# G503.net
KiCad netlist of a schematic drawn in EAGLE
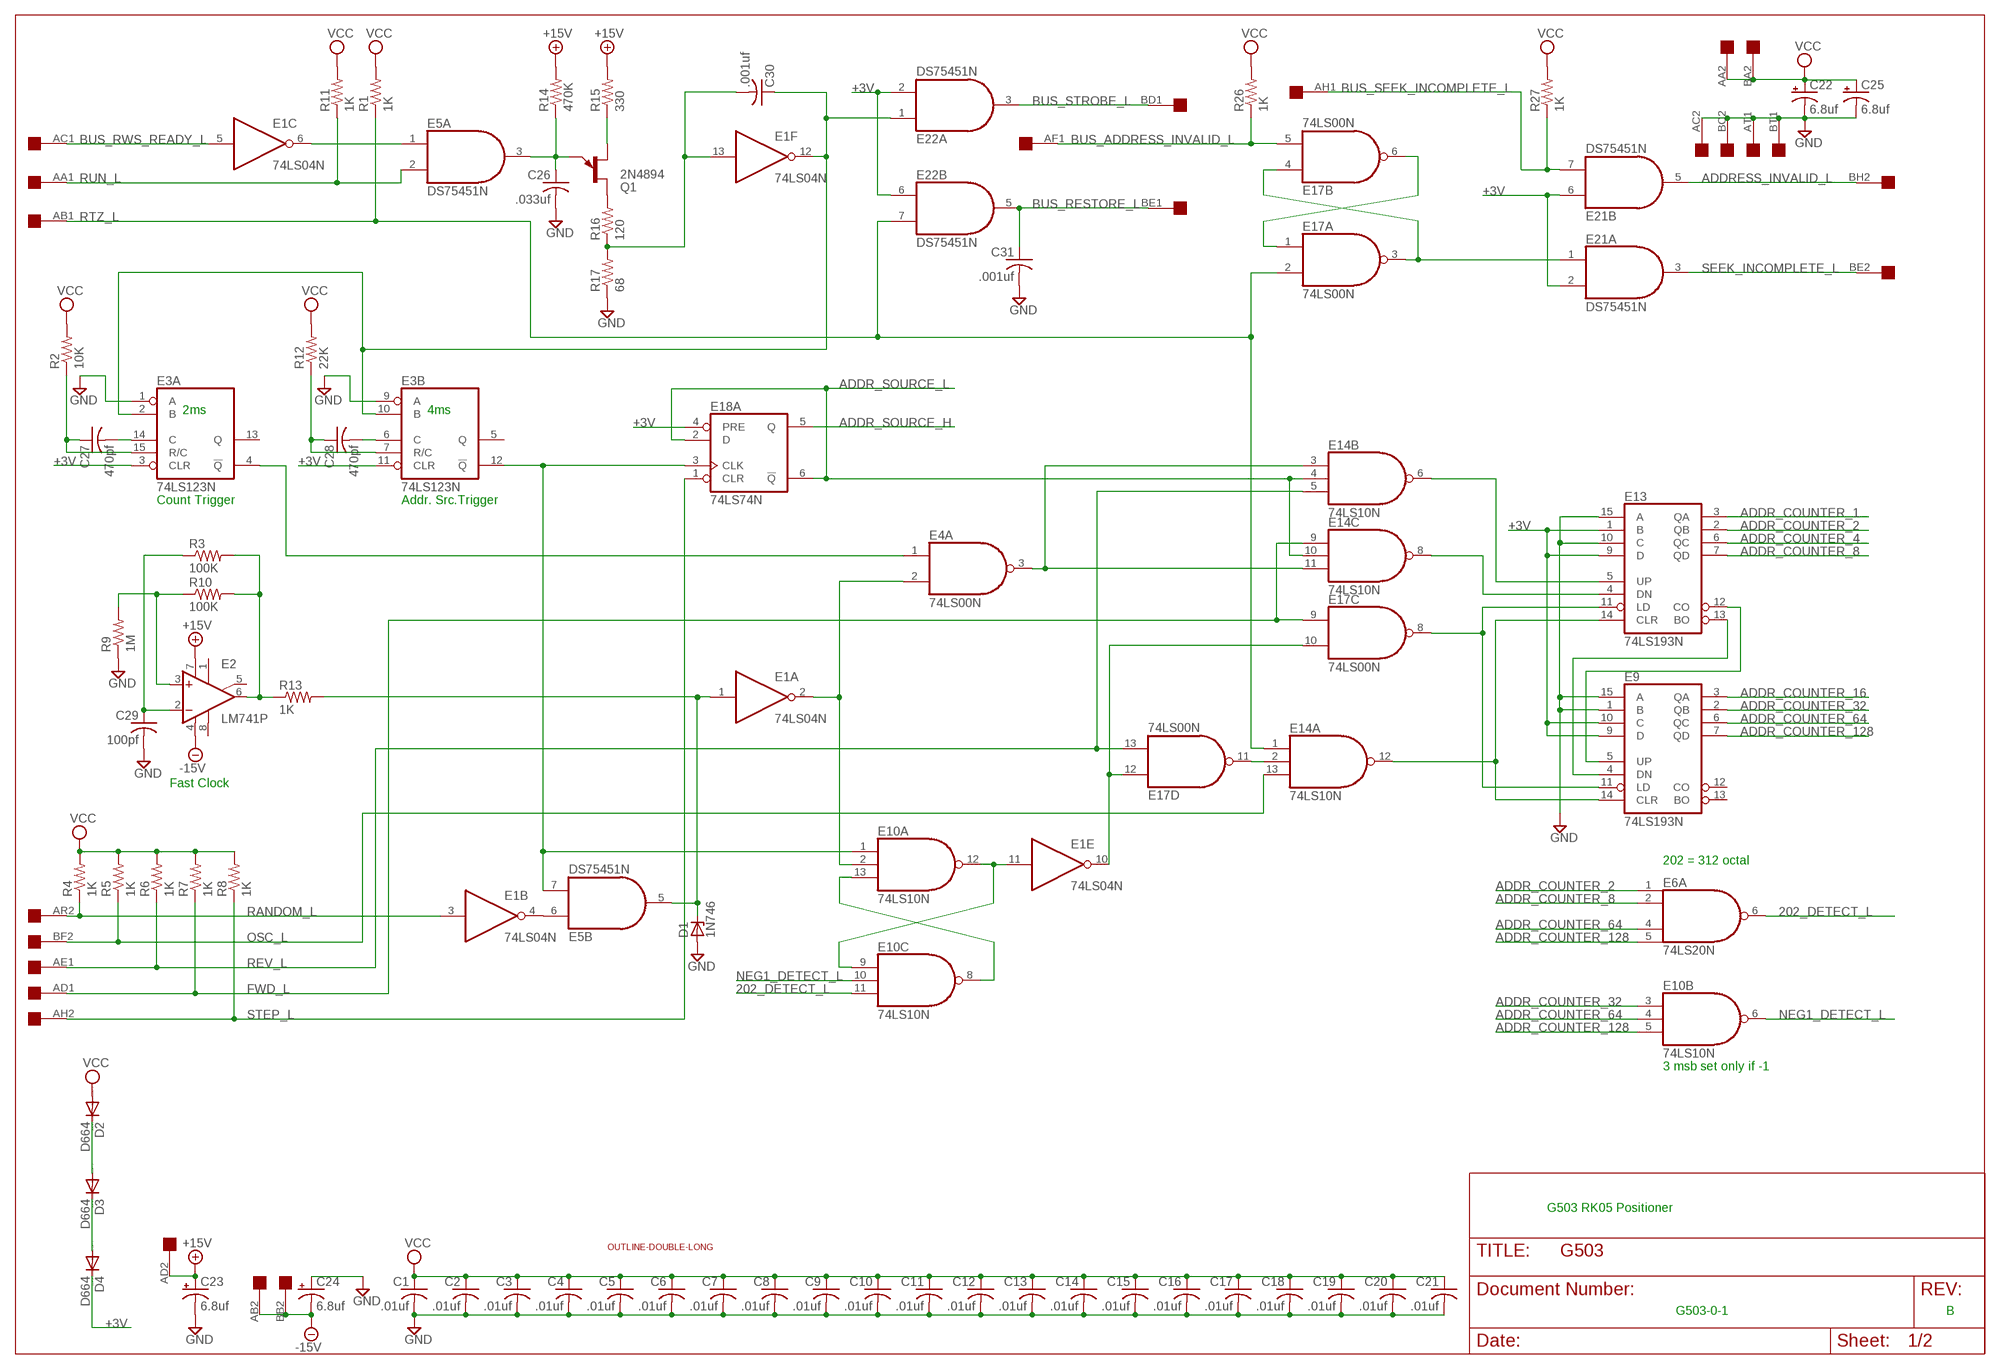
[diagram p0: schematic, sheet 1]
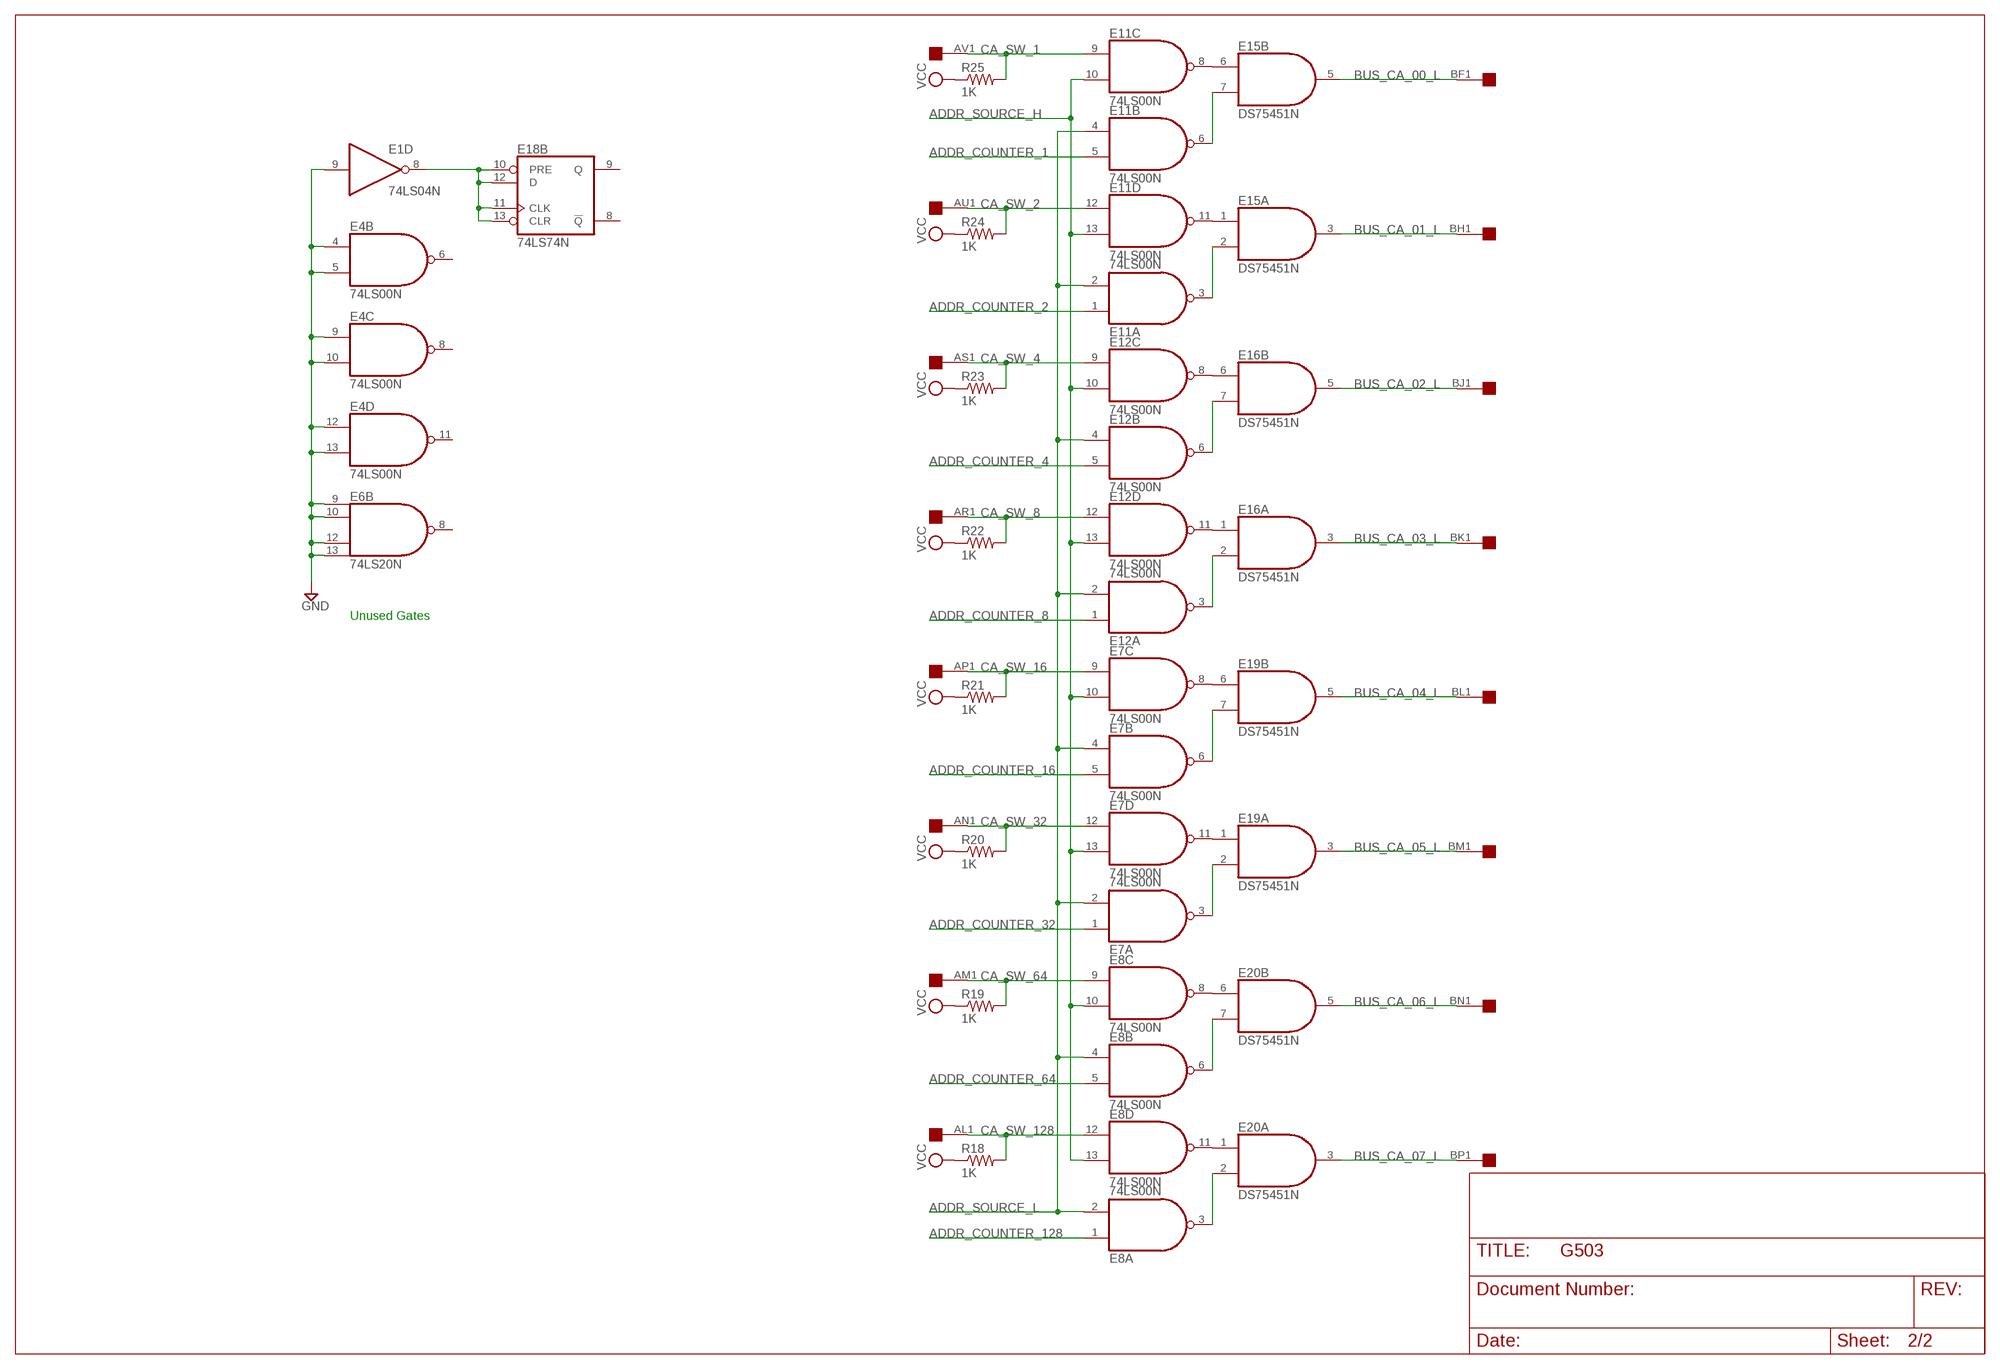
[diagram p1: schematic, sheet 2]

(export (version "E")
  (design (tool "Eeschema 10.0.6"))
  (components
    (comp (ref "AB03")
      (value "DOUBLE")
      (footprint "eagle-import:EDGE-CON4")
      (libsource (lib "eagle-import") (part "DOUBLE"))
    )
    (comp (ref "C1")
      (value ".01uf")
      (footprint "eagle-import:C075-032X103")
      (libsource (lib "eagle-import") (part "C-US075-032X103"))
    )
    (comp (ref "C2")
      (value ".01uf")
      (footprint "eagle-import:C075-032X103")
      (libsource (lib "eagle-import") (part "C-US075-032X103"))
    )
    (comp (ref "C3")
      (value ".01uf")
      (footprint "eagle-import:C075-032X103")
      (libsource (lib "eagle-import") (part "C-US075-032X103"))
    )
    (comp (ref "C4")
      (value ".01uf")
      (footprint "eagle-import:C075-032X103")
      (libsource (lib "eagle-import") (part "C-US075-032X103"))
    )
    (comp (ref "C5")
      (value ".01uf")
      (footprint "eagle-import:C075-032X103")
      (libsource (lib "eagle-import") (part "C-US075-032X103"))
    )
    (comp (ref "C6")
      (value ".01uf")
      (footprint "eagle-import:C075-032X103")
      (libsource (lib "eagle-import") (part "C-US075-032X103"))
    )
    (comp (ref "C7")
      (value ".01uf")
      (footprint "eagle-import:C075-032X103")
      (libsource (lib "eagle-import") (part "C-US075-032X103"))
    )
    (comp (ref "C8")
      (value ".01uf")
      (footprint "eagle-import:C075-032X103")
      (libsource (lib "eagle-import") (part "C-US075-032X103"))
    )
    (comp (ref "C9")
      (value ".01uf")
      (footprint "eagle-import:C075-032X103")
      (libsource (lib "eagle-import") (part "C-US075-032X103"))
    )
    (comp (ref "C10")
      (value ".01uf")
      (footprint "eagle-import:C075-032X103")
      (libsource (lib "eagle-import") (part "C-US075-032X103"))
    )
    (comp (ref "C11")
      (value ".01uf")
      (footprint "eagle-import:C075-032X103")
      (libsource (lib "eagle-import") (part "C-US075-032X103"))
    )
    (comp (ref "C12")
      (value ".01uf")
      (footprint "eagle-import:C075-032X103")
      (libsource (lib "eagle-import") (part "C-US075-032X103"))
    )
    (comp (ref "C13")
      (value ".01uf")
      (footprint "eagle-import:C075-032X103")
      (libsource (lib "eagle-import") (part "C-US075-032X103"))
    )
    (comp (ref "C14")
      (value ".01uf")
      (footprint "eagle-import:C075-032X103")
      (libsource (lib "eagle-import") (part "C-US075-032X103"))
    )
    (comp (ref "C15")
      (value ".01uf")
      (footprint "eagle-import:C075-032X103")
      (libsource (lib "eagle-import") (part "C-US075-032X103"))
    )
    (comp (ref "C16")
      (value ".01uf")
      (footprint "eagle-import:C075-032X103")
      (libsource (lib "eagle-import") (part "C-US075-032X103"))
    )
    (comp (ref "C17")
      (value ".01uf")
      (footprint "eagle-import:C075-032X103")
      (libsource (lib "eagle-import") (part "C-US075-032X103"))
    )
    (comp (ref "C18")
      (value ".01uf")
      (footprint "eagle-import:C075-032X103")
      (libsource (lib "eagle-import") (part "C-US075-032X103"))
    )
    (comp (ref "C19")
      (value ".01uf")
      (footprint "eagle-import:C075-032X103")
      (libsource (lib "eagle-import") (part "C-US075-032X103"))
    )
    (comp (ref "C20")
      (value ".01uf")
      (footprint "eagle-import:C075-032X103")
      (libsource (lib "eagle-import") (part "C-US075-032X103"))
    )
    (comp (ref "C21")
      (value ".01uf")
      (footprint "eagle-import:C075-032X103")
      (libsource (lib "eagle-import") (part "C-US075-032X103"))
    )
    (comp (ref "C22")
      (value "6.8uf")
      (footprint "eagle-import:E25-9")
      (libsource (lib "eagle-import") (part "CPOL-USE25-9AXIAL"))
    )
    (comp (ref "C23")
      (value "6.8uf")
      (footprint "eagle-import:E25-9")
      (libsource (lib "eagle-import") (part "CPOL-USE25-9AXIAL"))
    )
    (comp (ref "C24")
      (value "6.8uf")
      (footprint "eagle-import:E25-9")
      (libsource (lib "eagle-import") (part "CPOL-USE25-9AXIAL"))
    )
    (comp (ref "C25")
      (value "6.8uf")
      (footprint "eagle-import:E25-9")
      (libsource (lib "eagle-import") (part "CPOL-USE25-9AXIAL"))
    )
    (comp (ref "C26")
      (value ".033uf")
      (footprint "eagle-import:C075-032X103")
      (libsource (lib "eagle-import") (part "C-US075-032X103"))
    )
    (comp (ref "C27")
      (value "470pf")
      (footprint "eagle-import:C075-032X103")
      (libsource (lib "eagle-import") (part "C-US075-032X103"))
    )
    (comp (ref "C28")
      (value "470pf")
      (footprint "eagle-import:C075-032X103")
      (libsource (lib "eagle-import") (part "C-US075-032X103"))
    )
    (comp (ref "C29")
      (value "100pf")
      (footprint "eagle-import:C075-032X103")
      (libsource (lib "eagle-import") (part "C-US075-032X103"))
    )
    (comp (ref "C30")
      (value ".001uf")
      (footprint "eagle-import:C075-032X103")
      (libsource (lib "eagle-import") (part "C-US075-032X103"))
    )
    (comp (ref "C31")
      (value ".001uf")
      (footprint "eagle-import:C075-032X103")
      (libsource (lib "eagle-import") (part "C-US075-032X103"))
    )
    (comp (ref "D1")
      (value "1N746")
      (footprint "eagle-import:DO35Z10")
      (libsource (lib "eagle-import") (part "ZENER-DIODEDO35Z10"))
    )
    (comp (ref "D2")
      (value "D664")
      (footprint "eagle-import:DO35-10")
      (libsource (lib "eagle-import") (part "1N4148DO35-10"))
    )
    (comp (ref "D3")
      (value "D664")
      (footprint "eagle-import:DO35-10")
      (libsource (lib "eagle-import") (part "1N4148DO35-10"))
    )
    (comp (ref "D4")
      (value "D664")
      (footprint "eagle-import:DO35-10")
      (libsource (lib "eagle-import") (part "1N4148DO35-10"))
    )
    (comp (ref "E1")
      (value "74LS04N")
      (footprint "eagle-import:DIL14")
      (libsource (lib "eagle-import") (part "7404NLS"))
    )
    (comp (ref "E2")
      (value "LM741P")
      (footprint "eagle-import:DIL08")
      (libsource (lib "eagle-import") (part "741PLM"))
    )
    (comp (ref "E3")
      (value "74LS123N")
      (footprint "eagle-import:DIL16")
      (libsource (lib "eagle-import") (part "74123NLS"))
    )
    (comp (ref "E4")
      (value "74LS00N")
      (footprint "eagle-import:DIL14")
      (libsource (lib "eagle-import") (part "7400NLS"))
    )
    (comp (ref "E5")
      (value "DS75451N")
      (footprint "eagle-import:DIL08")
      (libsource (lib "eagle-import") (part "DS75451N"))
    )
    (comp (ref "E6")
      (value "74LS20N")
      (footprint "eagle-import:DIL14")
      (libsource (lib "eagle-import") (part "7420NLS"))
    )
    (comp (ref "E9")
      (value "74LS193N")
      (footprint "eagle-import:DIL16")
      (libsource (lib "eagle-import") (part "74193NLS"))
    )
    (comp (ref "E10")
      (value "74LS10N")
      (footprint "eagle-import:DIL14")
      (libsource (lib "eagle-import") (part "7410NAS"))
    )
    (comp (ref "E13")
      (value "74LS193N")
      (footprint "eagle-import:DIL16")
      (libsource (lib "eagle-import") (part "74193NLS"))
    )
    (comp (ref "E14")
      (value "74LS10N")
      (footprint "eagle-import:DIL14")
      (libsource (lib "eagle-import") (part "7410NAS"))
    )
    (comp (ref "E17")
      (value "74LS00N")
      (footprint "eagle-import:DIL14")
      (libsource (lib "eagle-import") (part "7400NLS"))
    )
    (comp (ref "E18")
      (value "74LS74N")
      (footprint "eagle-import:DIL14")
      (libsource (lib "eagle-import") (part "7474NLS"))
    )
    (comp (ref "E21")
      (value "DS75451N")
      (footprint "eagle-import:DIL08")
      (libsource (lib "eagle-import") (part "DS75451N"))
    )
    (comp (ref "E22")
      (value "DS75451N")
      (footprint "eagle-import:DIL08")
      (libsource (lib "eagle-import") (part "DS75451N"))
    )
    (comp (ref "Q1")
      (value "2N4894")
      (footprint "eagle-import:TO92E")
      (libsource (lib "eagle-import") (part "2N4870"))
    )
    (comp (ref "R1")
      (value "1K")
      (footprint "eagle-import:0207_10")
      (libsource (lib "eagle-import") (part "R-US_0207/10"))
    )
    (comp (ref "R2")
      (value "10K")
      (footprint "eagle-import:0207_10")
      (libsource (lib "eagle-import") (part "R-US_0207/10"))
    )
    (comp (ref "R3")
      (value "100K")
      (footprint "eagle-import:0207_10")
      (libsource (lib "eagle-import") (part "R-US_0207/10"))
    )
    (comp (ref "R4")
      (value "1K")
      (footprint "eagle-import:0207_10")
      (libsource (lib "eagle-import") (part "R-US_0207/10"))
    )
    (comp (ref "R5")
      (value "1K")
      (footprint "eagle-import:0207_10")
      (libsource (lib "eagle-import") (part "R-US_0207/10"))
    )
    (comp (ref "R6")
      (value "1K")
      (footprint "eagle-import:0207_10")
      (libsource (lib "eagle-import") (part "R-US_0207/10"))
    )
    (comp (ref "R7")
      (value "1K")
      (footprint "eagle-import:0207_10")
      (libsource (lib "eagle-import") (part "R-US_0207/10"))
    )
    (comp (ref "R8")
      (value "1K")
      (footprint "eagle-import:0207_10")
      (libsource (lib "eagle-import") (part "R-US_0207/10"))
    )
    (comp (ref "R9")
      (value "1M")
      (footprint "eagle-import:0207_10")
      (libsource (lib "eagle-import") (part "R-US_0207/10"))
    )
    (comp (ref "R10")
      (value "100K")
      (footprint "eagle-import:0207_10")
      (libsource (lib "eagle-import") (part "R-US_0207/10"))
    )
    (comp (ref "R11")
      (value "1K")
      (footprint "eagle-import:0207_10")
      (libsource (lib "eagle-import") (part "R-US_0207/10"))
    )
    (comp (ref "R12")
      (value "22K")
      (footprint "eagle-import:0207_10")
      (libsource (lib "eagle-import") (part "R-US_0207/10"))
    )
    (comp (ref "R13")
      (value "1K")
      (footprint "eagle-import:0207_10")
      (libsource (lib "eagle-import") (part "R-US_0207/10"))
    )
    (comp (ref "R14")
      (value "470K")
      (footprint "eagle-import:0207_10")
      (libsource (lib "eagle-import") (part "R-US_0207/10"))
    )
    (comp (ref "R15")
      (value "330")
      (footprint "eagle-import:0207_10")
      (libsource (lib "eagle-import") (part "R-US_0207/10"))
    )
    (comp (ref "R16")
      (value "120")
      (footprint "eagle-import:0207_10")
      (libsource (lib "eagle-import") (part "R-US_0207/10"))
    )
    (comp (ref "R17")
      (value "68")
      (footprint "eagle-import:0207_10")
      (libsource (lib "eagle-import") (part "R-US_0207/10"))
    )
    (comp (ref "R26")
      (value "1K")
      (footprint "eagle-import:0207_10")
      (libsource (lib "eagle-import") (part "R-US_0207/10"))
    )
    (comp (ref "R27")
      (value "1K")
      (footprint "eagle-import:0207_10")
      (libsource (lib "eagle-import") (part "R-US_0207/10"))
    )
    (comp (ref "U$1")
      (value "OUTLINE-DOUBLE-LONG")
      (footprint "eagle-import:DOUBLE-LONG")
      (libsource (lib "eagle-import") (part "OUTLINE-DOUBLE-LONG"))
    )
    (comp (ref "E7")
      (value "74LS00N")
      (footprint "eagle-import:DIL14")
      (libsource (lib "eagle-import") (part "7400NLS"))
    )
    (comp (ref "E8")
      (value "74LS00N")
      (footprint "eagle-import:DIL14")
      (libsource (lib "eagle-import") (part "7400NLS"))
    )
    (comp (ref "E11")
      (value "74LS00N")
      (footprint "eagle-import:DIL14")
      (libsource (lib "eagle-import") (part "7400NLS"))
    )
    (comp (ref "E12")
      (value "74LS00N")
      (footprint "eagle-import:DIL14")
      (libsource (lib "eagle-import") (part "7400NLS"))
    )
    (comp (ref "E15")
      (value "DS75451N")
      (footprint "eagle-import:DIL08")
      (libsource (lib "eagle-import") (part "DS75451N"))
    )
    (comp (ref "E16")
      (value "DS75451N")
      (footprint "eagle-import:DIL08")
      (libsource (lib "eagle-import") (part "DS75451N"))
    )
    (comp (ref "E19")
      (value "DS75451N")
      (footprint "eagle-import:DIL08")
      (libsource (lib "eagle-import") (part "DS75451N"))
    )
    (comp (ref "E20")
      (value "DS75451N")
      (footprint "eagle-import:DIL08")
      (libsource (lib "eagle-import") (part "DS75451N"))
    )
    (comp (ref "R18")
      (value "1K")
      (footprint "eagle-import:0207_10")
      (libsource (lib "eagle-import") (part "R-US_0207/10"))
    )
    (comp (ref "R19")
      (value "1K")
      (footprint "eagle-import:0207_10")
      (libsource (lib "eagle-import") (part "R-US_0207/10"))
    )
    (comp (ref "R20")
      (value "1K")
      (footprint "eagle-import:0207_10")
      (libsource (lib "eagle-import") (part "R-US_0207/10"))
    )
    (comp (ref "R21")
      (value "1K")
      (footprint "eagle-import:0207_10")
      (libsource (lib "eagle-import") (part "R-US_0207/10"))
    )
    (comp (ref "R22")
      (value "1K")
      (footprint "eagle-import:0207_10")
      (libsource (lib "eagle-import") (part "R-US_0207/10"))
    )
    (comp (ref "R23")
      (value "1K")
      (footprint "eagle-import:0207_10")
      (libsource (lib "eagle-import") (part "R-US_0207/10"))
    )
    (comp (ref "R24")
      (value "1K")
      (footprint "eagle-import:0207_10")
      (libsource (lib "eagle-import") (part "R-US_0207/10"))
    )
    (comp (ref "R25")
      (value "1K")
      (footprint "eagle-import:0207_10")
      (libsource (lib "eagle-import") (part "R-US_0207/10"))
    )
  )
  (nets
    (net (code "1") (name "+3V") (class "Default")
      (node (ref "D4") (pin "C") (pinfunction "C_C") (pintype "passive"))
      (node (ref "E13") (pin "1") (pinfunction "B_1") (pintype "input"))
      (node (ref "E13") (pin "9") (pinfunction "D_9") (pintype "input"))
      (node (ref "E18") (pin "4") (pinfunction "PRE_4") (pintype "input"))
      (node (ref "E21") (pin "2") (pinfunction "I1_2") (pintype "input"))
      (node (ref "E21") (pin "6") (pinfunction "I0_6") (pintype "input"))
      (node (ref "E22") (pin "2") (pinfunction "I1_2") (pintype "input"))
      (node (ref "E22") (pin "6") (pinfunction "I0_6") (pintype "input"))
      (node (ref "E3") (pin "11") (pinfunction "CLR_11") (pintype "input"))
      (node (ref "E3") (pin "3") (pinfunction "CLR_3") (pintype "input"))
      (node (ref "E9") (pin "10") (pinfunction "C_10") (pintype "input"))
      (node (ref "E9") (pin "9") (pinfunction "D_9") (pintype "input"))
    )
    (net (code "2") (name "+15V") (class "Default")
      (node (ref "AB03") (pin "AD2") (pinfunction "1_AD2") (pintype "bidirectional"))
      (node (ref "C23") (pin "+") (pinfunction "+_+") (pintype "passive"))
      (node (ref "E2") (pin "7") (pinfunction "V+_7") (pintype "power_in"))
      (node (ref "R14") (pin "2") (pinfunction "2_2") (pintype "passive"))
      (node (ref "R15") (pin "2") (pinfunction "2_2") (pintype "passive"))
    )
    (net (code "3") (name "-15V") (class "Default")
      (node (ref "AB03") (pin "AB2") (pinfunction "1_AB2") (pintype "bidirectional"))
      (node (ref "AB03") (pin "BB2") (pinfunction "1_BB2") (pintype "bidirectional"))
      (node (ref "C24") (pin "-") (pinfunction "-_-") (pintype "passive"))
      (node (ref "E2") (pin "4") (pinfunction "V-_4") (pintype "power_in"))
    )
    (net (code "4") (name "202_DETECT_L") (class "Default")
      (node (ref "E10") (pin "11") (pinfunction "I2_11") (pintype "input"))
      (node (ref "E6") (pin "6") (pinfunction "O_6") (pintype "output"))
    )
    (net (code "5") (name "ADDRESS_INVALID_L") (class "Default")
      (node (ref "AB03") (pin "BH2") (pinfunction "1_BH2") (pintype "bidirectional"))
      (node (ref "E21") (pin "5") (pinfunction "O_5") (pintype "open_collector"))
    )
    (net (code "6") (name "ADDR_COUNTER_1") (class "Default")
      (node (ref "E11") (pin "5") (pinfunction "I1_5") (pintype "input"))
      (node (ref "E13") (pin "3") (pinfunction "QA_3") (pintype "output"))
    )
    (net (code "7") (name "ADDR_COUNTER_2") (class "Default")
      (node (ref "E11") (pin "1") (pinfunction "I0_1") (pintype "input"))
      (node (ref "E13") (pin "2") (pinfunction "QB_2") (pintype "output"))
      (node (ref "E6") (pin "1") (pinfunction "I0_1") (pintype "input"))
    )
    (net (code "8") (name "ADDR_COUNTER_4") (class "Default")
      (node (ref "E12") (pin "5") (pinfunction "I1_5") (pintype "input"))
      (node (ref "E13") (pin "6") (pinfunction "QC_6") (pintype "output"))
    )
    (net (code "9") (name "ADDR_COUNTER_8") (class "Default")
      (node (ref "E12") (pin "1") (pinfunction "I0_1") (pintype "input"))
      (node (ref "E13") (pin "7") (pinfunction "QD_7") (pintype "output"))
      (node (ref "E6") (pin "2") (pinfunction "I1_2") (pintype "input"))
    )
    (net (code "10") (name "ADDR_COUNTER_16") (class "Default")
      (node (ref "E7") (pin "5") (pinfunction "I1_5") (pintype "input"))
      (node (ref "E9") (pin "3") (pinfunction "QA_3") (pintype "output"))
    )
    (net (code "11") (name "ADDR_COUNTER_32") (class "Default")
      (node (ref "E10") (pin "3") (pinfunction "I0_3") (pintype "input"))
      (node (ref "E7") (pin "1") (pinfunction "I0_1") (pintype "input"))
      (node (ref "E9") (pin "2") (pinfunction "QB_2") (pintype "output"))
    )
    (net (code "12") (name "ADDR_COUNTER_64") (class "Default")
      (node (ref "E10") (pin "4") (pinfunction "I1_4") (pintype "input"))
      (node (ref "E6") (pin "4") (pinfunction "I2_4") (pintype "input"))
      (node (ref "E8") (pin "5") (pinfunction "I1_5") (pintype "input"))
      (node (ref "E9") (pin "6") (pinfunction "QC_6") (pintype "output"))
    )
    (net (code "13") (name "ADDR_COUNTER_128") (class "Default")
      (node (ref "E10") (pin "5") (pinfunction "I2_5") (pintype "input"))
      (node (ref "E6") (pin "5") (pinfunction "I3_5") (pintype "input"))
      (node (ref "E8") (pin "1") (pinfunction "I0_1") (pintype "input"))
      (node (ref "E9") (pin "7") (pinfunction "QD_7") (pintype "output"))
    )
    (net (code "14") (name "ADDR_SOURCE_H") (class "Default")
      (node (ref "E11") (pin "10") (pinfunction "I1_10") (pintype "input"))
      (node (ref "E11") (pin "13") (pinfunction "I1_13") (pintype "input"))
      (node (ref "E12") (pin "10") (pinfunction "I1_10") (pintype "input"))
      (node (ref "E12") (pin "13") (pinfunction "I1_13") (pintype "input"))
      (node (ref "E18") (pin "5") (pinfunction "Q_5") (pintype "output"))
      (node (ref "E7") (pin "10") (pinfunction "I1_10") (pintype "input"))
      (node (ref "E7") (pin "13") (pinfunction "I1_13") (pintype "input"))
      (node (ref "E8") (pin "10") (pinfunction "I1_10") (pintype "input"))
      (node (ref "E8") (pin "13") (pinfunction "I1_13") (pintype "input"))
    )
    (net (code "15") (name "ADDR_SOURCE_L") (class "Default")
      (node (ref "E11") (pin "2") (pinfunction "I1_2") (pintype "input"))
      (node (ref "E11") (pin "4") (pinfunction "I0_4") (pintype "input"))
      (node (ref "E12") (pin "2") (pinfunction "I1_2") (pintype "input"))
      (node (ref "E12") (pin "4") (pinfunction "I0_4") (pintype "input"))
      (node (ref "E14") (pin "10") (pinfunction "I1_10") (pintype "input"))
      (node (ref "E14") (pin "4") (pinfunction "I1_4") (pintype "input"))
      (node (ref "E18") (pin "2") (pinfunction "D_2") (pintype "input"))
      (node (ref "E18") (pin "6") (pinfunction "~{Q}_6") (pintype "output"))
      (node (ref "E7") (pin "2") (pinfunction "I1_2") (pintype "input"))
      (node (ref "E7") (pin "4") (pinfunction "I0_4") (pintype "input"))
      (node (ref "E8") (pin "2") (pinfunction "I1_2") (pintype "input"))
      (node (ref "E8") (pin "4") (pinfunction "I0_4") (pintype "input"))
    )
    (net (code "16") (name "BUS_ADDRESS_INVALID_L") (class "Default")
      (node (ref "AB03") (pin "AF1") (pinfunction "1_AF1") (pintype "bidirectional"))
      (node (ref "E17") (pin "5") (pinfunction "I1_5") (pintype "input"))
      (node (ref "R26") (pin "1") (pinfunction "1_1") (pintype "passive"))
    )
    (net (code "17") (name "BUS_CA_00_L") (class "Default")
      (node (ref "AB03") (pin "BF1") (pinfunction "1_BF1") (pintype "bidirectional"))
      (node (ref "E15") (pin "5") (pinfunction "O_5") (pintype "open_collector"))
    )
    (net (code "18") (name "BUS_CA_01_L") (class "Default")
      (node (ref "AB03") (pin "BH1") (pinfunction "1_BH1") (pintype "bidirectional"))
      (node (ref "E15") (pin "3") (pinfunction "O_3") (pintype "open_collector"))
    )
    (net (code "19") (name "BUS_CA_02_L") (class "Default")
      (node (ref "AB03") (pin "BJ1") (pinfunction "1_BJ1") (pintype "bidirectional"))
      (node (ref "E16") (pin "5") (pinfunction "O_5") (pintype "open_collector"))
    )
    (net (code "20") (name "BUS_CA_03_L") (class "Default")
      (node (ref "AB03") (pin "BK1") (pinfunction "1_BK1") (pintype "bidirectional"))
      (node (ref "E16") (pin "3") (pinfunction "O_3") (pintype "open_collector"))
    )
    (net (code "21") (name "BUS_CA_04_L") (class "Default")
      (node (ref "AB03") (pin "BL1") (pinfunction "1_BL1") (pintype "bidirectional"))
      (node (ref "E19") (pin "5") (pinfunction "O_5") (pintype "open_collector"))
    )
    (net (code "22") (name "BUS_CA_05_L") (class "Default")
      (node (ref "AB03") (pin "BM1") (pinfunction "1_BM1") (pintype "bidirectional"))
      (node (ref "E19") (pin "3") (pinfunction "O_3") (pintype "open_collector"))
    )
    (net (code "23") (name "BUS_CA_06_L") (class "Default")
      (node (ref "AB03") (pin "BN1") (pinfunction "1_BN1") (pintype "bidirectional"))
      (node (ref "E20") (pin "5") (pinfunction "O_5") (pintype "open_collector"))
    )
    (net (code "24") (name "BUS_CA_07_L") (class "Default")
      (node (ref "AB03") (pin "BP1") (pinfunction "1_BP1") (pintype "bidirectional"))
      (node (ref "E20") (pin "3") (pinfunction "O_3") (pintype "open_collector"))
    )
    (net (code "25") (name "BUS_RESTORE_L") (class "Default")
      (node (ref "AB03") (pin "BE1") (pinfunction "1_BE1") (pintype "bidirectional"))
      (node (ref "C31") (pin "1") (pinfunction "1_1") (pintype "passive"))
      (node (ref "E22") (pin "5") (pinfunction "O_5") (pintype "open_collector"))
    )
    (net (code "26") (name "BUS_RWS_READY_L") (class "Default")
      (node (ref "AB03") (pin "AC1") (pinfunction "1_AC1") (pintype "bidirectional"))
      (node (ref "E1") (pin "5") (pinfunction "I_5") (pintype "input"))
    )
    (net (code "27") (name "BUS_SEEK_INCOMPLETE_L") (class "Default")
      (node (ref "AB03") (pin "AH1") (pinfunction "1_AH1") (pintype "bidirectional"))
      (node (ref "E21") (pin "7") (pinfunction "I1_7") (pintype "input"))
      (node (ref "R27") (pin "1") (pinfunction "1_1") (pintype "passive"))
    )
    (net (code "28") (name "BUS_STROBE_L") (class "Default")
      (node (ref "AB03") (pin "BD1") (pinfunction "1_BD1") (pintype "bidirectional"))
      (node (ref "E22") (pin "3") (pinfunction "O_3") (pintype "open_collector"))
    )
    (net (code "29") (name "CA_SW_1") (class "Default")
      (node (ref "AB03") (pin "AV1") (pinfunction "1_AV1") (pintype "bidirectional"))
      (node (ref "E11") (pin "9") (pinfunction "I0_9") (pintype "input"))
      (node (ref "R25") (pin "2") (pinfunction "2_2") (pintype "passive"))
    )
    (net (code "30") (name "CA_SW_2") (class "Default")
      (node (ref "AB03") (pin "AU1") (pinfunction "1_AU1") (pintype "bidirectional"))
      (node (ref "E11") (pin "12") (pinfunction "I0_12") (pintype "input"))
      (node (ref "R24") (pin "2") (pinfunction "2_2") (pintype "passive"))
    )
    (net (code "31") (name "CA_SW_4") (class "Default")
      (node (ref "AB03") (pin "AS1") (pinfunction "1_AS1") (pintype "bidirectional"))
      (node (ref "E12") (pin "9") (pinfunction "I0_9") (pintype "input"))
      (node (ref "R23") (pin "2") (pinfunction "2_2") (pintype "passive"))
    )
    (net (code "32") (name "CA_SW_8") (class "Default")
      (node (ref "AB03") (pin "AR1") (pinfunction "1_AR1") (pintype "bidirectional"))
      (node (ref "E12") (pin "12") (pinfunction "I0_12") (pintype "input"))
      (node (ref "R22") (pin "2") (pinfunction "2_2") (pintype "passive"))
    )
    (net (code "33") (name "CA_SW_16") (class "Default")
      (node (ref "AB03") (pin "AP1") (pinfunction "1_AP1") (pintype "bidirectional"))
      (node (ref "E7") (pin "9") (pinfunction "I0_9") (pintype "input"))
      (node (ref "R21") (pin "2") (pinfunction "2_2") (pintype "passive"))
    )
    (net (code "34") (name "CA_SW_32") (class "Default")
      (node (ref "AB03") (pin "AN1") (pinfunction "1_AN1") (pintype "bidirectional"))
      (node (ref "E7") (pin "12") (pinfunction "I0_12") (pintype "input"))
      (node (ref "R20") (pin "2") (pinfunction "2_2") (pintype "passive"))
    )
    (net (code "35") (name "CA_SW_64") (class "Default")
      (node (ref "AB03") (pin "AM1") (pinfunction "1_AM1") (pintype "bidirectional"))
      (node (ref "E8") (pin "9") (pinfunction "I0_9") (pintype "input"))
      (node (ref "R19") (pin "2") (pinfunction "2_2") (pintype "passive"))
    )
    (net (code "36") (name "CA_SW_128") (class "Default")
      (node (ref "AB03") (pin "AL1") (pinfunction "1_AL1") (pintype "bidirectional"))
      (node (ref "E8") (pin "12") (pinfunction "I0_12") (pintype "input"))
      (node (ref "R18") (pin "2") (pinfunction "2_2") (pintype "passive"))
    )
    (net (code "37") (name "FWD_L") (class "Default")
      (node (ref "AB03") (pin "AD1") (pinfunction "1_AD1") (pintype "bidirectional"))
      (node (ref "E14") (pin "9") (pinfunction "I0_9") (pintype "input"))
      (node (ref "E17") (pin "9") (pinfunction "I0_9") (pintype "input"))
      (node (ref "R7") (pin "1") (pinfunction "1_1") (pintype "passive"))
    )
    (net (code "38") (name "GND") (class "Default")
      (node (ref "AB03") (pin "AC2") (pinfunction "1_AC2") (pintype "bidirectional"))
      (node (ref "AB03") (pin "AT1") (pinfunction "1_AT1") (pintype "bidirectional"))
      (node (ref "AB03") (pin "BC2") (pinfunction "1_BC2") (pintype "bidirectional"))
      (node (ref "AB03") (pin "BT1") (pinfunction "1_BT1") (pintype "bidirectional"))
      (node (ref "C1") (pin "2") (pinfunction "2_2") (pintype "passive"))
      (node (ref "C10") (pin "2") (pinfunction "2_2") (pintype "passive"))
      (node (ref "C11") (pin "2") (pinfunction "2_2") (pintype "passive"))
      (node (ref "C12") (pin "2") (pinfunction "2_2") (pintype "passive"))
      (node (ref "C13") (pin "2") (pinfunction "2_2") (pintype "passive"))
      (node (ref "C14") (pin "2") (pinfunction "2_2") (pintype "passive"))
      (node (ref "C15") (pin "2") (pinfunction "2_2") (pintype "passive"))
      (node (ref "C16") (pin "2") (pinfunction "2_2") (pintype "passive"))
      (node (ref "C17") (pin "2") (pinfunction "2_2") (pintype "passive"))
      (node (ref "C18") (pin "2") (pinfunction "2_2") (pintype "passive"))
      (node (ref "C19") (pin "2") (pinfunction "2_2") (pintype "passive"))
      (node (ref "C2") (pin "2") (pinfunction "2_2") (pintype "passive"))
      (node (ref "C20") (pin "2") (pinfunction "2_2") (pintype "passive"))
      (node (ref "C21") (pin "2") (pinfunction "2_2") (pintype "passive"))
      (node (ref "C22") (pin "-") (pinfunction "-_-") (pintype "passive"))
      (node (ref "C23") (pin "-") (pinfunction "-_-") (pintype "passive"))
      (node (ref "C24") (pin "+") (pinfunction "+_+") (pintype "passive"))
      (node (ref "C25") (pin "-") (pinfunction "-_-") (pintype "passive"))
      (node (ref "C26") (pin "2") (pinfunction "2_2") (pintype "passive"))
      (node (ref "C29") (pin "2") (pinfunction "2_2") (pintype "passive"))
      (node (ref "C3") (pin "2") (pinfunction "2_2") (pintype "passive"))
      (node (ref "C31") (pin "2") (pinfunction "2_2") (pintype "passive"))
      (node (ref "C4") (pin "2") (pinfunction "2_2") (pintype "passive"))
      (node (ref "C5") (pin "2") (pinfunction "2_2") (pintype "passive"))
      (node (ref "C6") (pin "2") (pinfunction "2_2") (pintype "passive"))
      (node (ref "C7") (pin "2") (pinfunction "2_2") (pintype "passive"))
      (node (ref "C8") (pin "2") (pinfunction "2_2") (pintype "passive"))
      (node (ref "C9") (pin "2") (pinfunction "2_2") (pintype "passive"))
      (node (ref "D1") (pin "A") (pinfunction "A_A") (pintype "passive"))
      (node (ref "E1") (pin "9") (pinfunction "I_9") (pintype "input"))
      (node (ref "E13") (pin "10") (pinfunction "C_10") (pintype "input"))
      (node (ref "E13") (pin "15") (pinfunction "A_15") (pintype "input"))
      (node (ref "E3") (pin "1") (pinfunction "A_1") (pintype "input"))
      (node (ref "E3") (pin "9") (pinfunction "A_9") (pintype "input"))
      (node (ref "E4") (pin "10") (pinfunction "I1_10") (pintype "input"))
      (node (ref "E4") (pin "12") (pinfunction "I0_12") (pintype "input"))
      (node (ref "E4") (pin "13") (pinfunction "I1_13") (pintype "input"))
      (node (ref "E4") (pin "4") (pinfunction "I0_4") (pintype "input"))
      (node (ref "E4") (pin "5") (pinfunction "I1_5") (pintype "input"))
      (node (ref "E4") (pin "9") (pinfunction "I0_9") (pintype "input"))
      (node (ref "E6") (pin "10") (pinfunction "I1_10") (pintype "input"))
      (node (ref "E6") (pin "12") (pinfunction "I2_12") (pintype "input"))
      (node (ref "E6") (pin "13") (pinfunction "I3_13") (pintype "input"))
      (node (ref "E6") (pin "9") (pinfunction "I0_9") (pintype "input"))
      (node (ref "E9") (pin "1") (pinfunction "B_1") (pintype "input"))
      (node (ref "E9") (pin "15") (pinfunction "A_15") (pintype "input"))
      (node (ref "R17") (pin "1") (pinfunction "1_1") (pintype "passive"))
      (node (ref "R9") (pin "1") (pinfunction "1_1") (pintype "passive"))
    )
    (net (code "39") (name "NEG1_DETECT_L") (class "Default")
      (node (ref "E10") (pin "10") (pinfunction "I1_10") (pintype "input"))
      (node (ref "E10") (pin "6") (pinfunction "O_6") (pintype "output"))
    )
    (net (code "40") (name "Net-(D2-PadC)") (class "Default")
      (node (ref "D2") (pin "C") (pinfunction "C_C") (pintype "passive"))
      (node (ref "D3") (pin "A") (pinfunction "A_A") (pintype "passive"))
    )
    (net (code "41") (name "Net-(D3-PadC)") (class "Default")
      (node (ref "D3") (pin "C") (pinfunction "C_C") (pintype "passive"))
      (node (ref "D4") (pin "A") (pinfunction "A_A") (pintype "passive"))
    )
    (net (code "42") (name "Net-(E1A-I)") (class "Default")
      (node (ref "D1") (pin "C") (pinfunction "C_C") (pintype "passive"))
      (node (ref "E1") (pin "1") (pinfunction "I_1") (pintype "input"))
      (node (ref "E5") (pin "5") (pinfunction "O_5") (pintype "open_collector"))
      (node (ref "R13") (pin "2") (pinfunction "2_2") (pintype "passive"))
    )
    (net (code "43") (name "Net-(E1B-O)") (class "Default")
      (node (ref "E1") (pin "4") (pinfunction "O_4") (pintype "output"))
      (node (ref "E5") (pin "6") (pinfunction "I0_6") (pintype "input"))
    )
    (net (code "44") (name "Net-(E1C-O)") (class "Default")
      (node (ref "E1") (pin "6") (pinfunction "O_6") (pintype "output"))
      (node (ref "E5") (pin "1") (pinfunction "I0_1") (pintype "input"))
    )
    (net (code "45") (name "Net-(E1F-I)") (class "Default")
      (node (ref "C30") (pin "2") (pinfunction "2_2") (pintype "passive"))
      (node (ref "E1") (pin "13") (pinfunction "I_13") (pintype "input"))
      (node (ref "R16") (pin "1") (pinfunction "1_1") (pintype "passive"))
      (node (ref "R17") (pin "2") (pinfunction "2_2") (pintype "passive"))
    )
    (net (code "46") (name "Net-(E1F-O)") (class "Default")
      (node (ref "C30") (pin "1") (pinfunction "1_1") (pintype "passive"))
      (node (ref "E1") (pin "12") (pinfunction "O_12") (pintype "output"))
      (node (ref "E22") (pin "1") (pinfunction "I0_1") (pintype "input"))
      (node (ref "E3") (pin "10") (pinfunction "B_10") (pintype "input"))
      (node (ref "E3") (pin "2") (pinfunction "B_2") (pintype "input"))
    )
    (net (code "47") (name "Net-(E2-+IN)") (class "Default")
      (node (ref "E2") (pin "3") (pinfunction "+IN_3") (pintype "input"))
      (node (ref "R10") (pin "1") (pinfunction "1_1") (pintype "passive"))
      (node (ref "R9") (pin "2") (pinfunction "2_2") (pintype "passive"))
    )
    (net (code "48") (name "Net-(E2--IN)") (class "Default")
      (node (ref "C29") (pin "1") (pinfunction "1_1") (pintype "passive"))
      (node (ref "E2") (pin "2") (pinfunction "-IN_2") (pintype "input"))
      (node (ref "R3") (pin "1") (pinfunction "1_1") (pintype "passive"))
    )
    (net (code "49") (name "Net-(E2-OUT)") (class "Default")
      (node (ref "E2") (pin "6") (pinfunction "OUT_6") (pintype "output"))
      (node (ref "R10") (pin "2") (pinfunction "2_2") (pintype "passive"))
      (node (ref "R13") (pin "1") (pinfunction "1_1") (pintype "passive"))
      (node (ref "R3") (pin "2") (pinfunction "2_2") (pintype "passive"))
    )
    (net (code "50") (name "Net-(E3A-C)") (class "Default")
      (node (ref "C27") (pin "2") (pinfunction "2_2") (pintype "passive"))
      (node (ref "E3") (pin "14") (pinfunction "C_14") (pintype "input"))
    )
    (net (code "51") (name "Net-(E3A-R{slash}C)") (class "Default")
      (node (ref "C27") (pin "1") (pinfunction "1_1") (pintype "passive"))
      (node (ref "E3") (pin "15") (pinfunction "R/C_15") (pintype "input"))
      (node (ref "R2") (pin "1") (pinfunction "1_1") (pintype "passive"))
    )
    (net (code "52") (name "Net-(E3A-~{Q})") (class "Default")
      (node (ref "E3") (pin "4") (pinfunction "~{Q}_4") (pintype "output"))
      (node (ref "E4") (pin "1") (pinfunction "I0_1") (pintype "input"))
    )
    (net (code "53") (name "Net-(E3B-C)") (class "Default")
      (node (ref "C28") (pin "2") (pinfunction "2_2") (pintype "passive"))
      (node (ref "E3") (pin "6") (pinfunction "C_6") (pintype "input"))
    )
    (net (code "54") (name "Net-(E3B-R{slash}C)") (class "Default")
      (node (ref "C28") (pin "1") (pinfunction "1_1") (pintype "passive"))
      (node (ref "E3") (pin "7") (pinfunction "R/C_7") (pintype "input"))
      (node (ref "R12") (pin "1") (pinfunction "1_1") (pintype "passive"))
    )
    (net (code "55") (name "Net-(E5A-O)") (class "Default")
      (node (ref "C26") (pin "1") (pinfunction "1_1") (pintype "passive"))
      (node (ref "E5") (pin "3") (pinfunction "O_3") (pintype "open_collector"))
      (node (ref "Q1") (pin "E") (pinfunction "E_E") (pintype "passive"))
      (node (ref "R14") (pin "1") (pinfunction "1_1") (pintype "passive"))
    )
    (net (code "56") (name "Net-(E10A-I0)") (class "Default")
      (node (ref "E10") (pin "1") (pinfunction "I0_1") (pintype "input"))
      (node (ref "E18") (pin "3") (pinfunction "CLK_3") (pintype "input"))
      (node (ref "E3") (pin "12") (pinfunction "~{Q}_12") (pintype "output"))
      (node (ref "E5") (pin "7") (pinfunction "I1_7") (pintype "input"))
    )
    (net (code "57") (name "Net-(E10A-I1)") (class "Default")
      (node (ref "E1") (pin "2") (pinfunction "O_2") (pintype "output"))
      (node (ref "E10") (pin "2") (pinfunction "I1_2") (pintype "input"))
      (node (ref "E4") (pin "2") (pinfunction "I1_2") (pintype "input"))
    )
    (net (code "58") (name "Net-(E10A-I2)") (class "Default")
      (node (ref "E10") (pin "13") (pinfunction "I2_13") (pintype "input"))
      (node (ref "E10") (pin "8") (pinfunction "O_8") (pintype "output"))
    )
    (net (code "59") (name "Net-(E10A-O)") (class "Default")
      (node (ref "E1") (pin "11") (pinfunction "I_11") (pintype "input"))
      (node (ref "E10") (pin "12") (pinfunction "O_12") (pintype "output"))
      (node (ref "E10") (pin "9") (pinfunction "I0_9") (pintype "input"))
    )
    (net (code "60") (name "Net-(E11A-O)") (class "Default")
      (node (ref "E11") (pin "3") (pinfunction "O_3") (pintype "output"))
      (node (ref "E15") (pin "2") (pinfunction "I1_2") (pintype "input"))
    )
    (net (code "61") (name "Net-(E11B-O)") (class "Default")
      (node (ref "E11") (pin "6") (pinfunction "O_6") (pintype "output"))
      (node (ref "E15") (pin "7") (pinfunction "I1_7") (pintype "input"))
    )
    (net (code "62") (name "Net-(E11C-O)") (class "Default")
      (node (ref "E11") (pin "8") (pinfunction "O_8") (pintype "output"))
      (node (ref "E15") (pin "6") (pinfunction "I0_6") (pintype "input"))
    )
    (net (code "63") (name "Net-(E11D-O)") (class "Default")
      (node (ref "E11") (pin "11") (pinfunction "O_11") (pintype "output"))
      (node (ref "E15") (pin "1") (pinfunction "I0_1") (pintype "input"))
    )
    (net (code "64") (name "Net-(E12A-O)") (class "Default")
      (node (ref "E12") (pin "3") (pinfunction "O_3") (pintype "output"))
      (node (ref "E16") (pin "2") (pinfunction "I1_2") (pintype "input"))
    )
    (net (code "65") (name "Net-(E12B-O)") (class "Default")
      (node (ref "E12") (pin "6") (pinfunction "O_6") (pintype "output"))
      (node (ref "E16") (pin "7") (pinfunction "I1_7") (pintype "input"))
    )
    (net (code "66") (name "Net-(E12C-O)") (class "Default")
      (node (ref "E12") (pin "8") (pinfunction "O_8") (pintype "output"))
      (node (ref "E16") (pin "6") (pinfunction "I0_6") (pintype "input"))
    )
    (net (code "67") (name "Net-(E12D-O)") (class "Default")
      (node (ref "E12") (pin "11") (pinfunction "O_11") (pintype "output"))
      (node (ref "E16") (pin "1") (pinfunction "I0_1") (pintype "input"))
    )
    (net (code "68") (name "Net-(E13A-BO)") (class "Default")
      (node (ref "E13") (pin "13") (pinfunction "BO_13") (pintype "output"))
      (node (ref "E9") (pin "4") (pinfunction "DN_4") (pintype "input"))
    )
    (net (code "69") (name "Net-(E13A-CLR)") (class "Default")
      (node (ref "E13") (pin "14") (pinfunction "CLR_14") (pintype "input"))
      (node (ref "E14") (pin "12") (pinfunction "O_12") (pintype "output"))
      (node (ref "E9") (pin "14") (pinfunction "CLR_14") (pintype "input"))
    )
    (net (code "70") (name "Net-(E13A-CO)") (class "Default")
      (node (ref "E13") (pin "12") (pinfunction "CO_12") (pintype "output"))
      (node (ref "E9") (pin "5") (pinfunction "UP_5") (pintype "input"))
    )
    (net (code "71") (name "Net-(E13A-DN)") (class "Default")
      (node (ref "E13") (pin "4") (pinfunction "DN_4") (pintype "input"))
      (node (ref "E14") (pin "8") (pinfunction "O_8") (pintype "output"))
    )
    (net (code "72") (name "Net-(E13A-LD)") (class "Default")
      (node (ref "E13") (pin "11") (pinfunction "LD_11") (pintype "input"))
      (node (ref "E17") (pin "8") (pinfunction "O_8") (pintype "output"))
      (node (ref "E9") (pin "11") (pinfunction "LD_11") (pintype "input"))
    )
    (net (code "73") (name "Net-(E13A-UP)") (class "Default")
      (node (ref "E13") (pin "5") (pinfunction "UP_5") (pintype "input"))
      (node (ref "E14") (pin "6") (pinfunction "O_6") (pintype "output"))
    )
    (net (code "74") (name "Net-(E14A-I1)") (class "Default")
      (node (ref "E14") (pin "2") (pinfunction "I1_2") (pintype "input"))
      (node (ref "E17") (pin "11") (pinfunction "O_11") (pintype "output"))
    )
    (net (code "75") (name "Net-(E14B-I0)") (class "Default")
      (node (ref "E14") (pin "11") (pinfunction "I2_11") (pintype "input"))
      (node (ref "E14") (pin "3") (pinfunction "I0_3") (pintype "input"))
      (node (ref "E4") (pin "3") (pinfunction "O_3") (pintype "output"))
    )
    (net (code "76") (name "Net-(E17A-I0)") (class "Default")
      (node (ref "E17") (pin "1") (pinfunction "I0_1") (pintype "input"))
      (node (ref "E17") (pin "6") (pinfunction "O_6") (pintype "output"))
    )
    (net (code "77") (name "Net-(E17A-O)") (class "Default")
      (node (ref "E17") (pin "3") (pinfunction "O_3") (pintype "output"))
      (node (ref "E17") (pin "4") (pinfunction "I0_4") (pintype "input"))
      (node (ref "E21") (pin "1") (pinfunction "I0_1") (pintype "input"))
    )
    (net (code "78") (name "Net-(E17C-I1)") (class "Default")
      (node (ref "E1") (pin "10") (pinfunction "O_10") (pintype "output"))
      (node (ref "E17") (pin "10") (pinfunction "I1_10") (pintype "input"))
      (node (ref "E17") (pin "12") (pinfunction "I0_12") (pintype "input"))
    )
    (net (code "79") (name "Net-(E18B-CLK)") (class "Default")
      (node (ref "E1") (pin "8") (pinfunction "O_8") (pintype "output"))
      (node (ref "E18") (pin "10") (pinfunction "PRE_10") (pintype "input"))
      (node (ref "E18") (pin "11") (pinfunction "CLK_11") (pintype "input"))
      (node (ref "E18") (pin "12") (pinfunction "D_12") (pintype "input"))
      (node (ref "E18") (pin "13") (pinfunction "CLR_13") (pintype "input"))
    )
    (net (code "80") (name "Net-(E19A-I0)") (class "Default")
      (node (ref "E19") (pin "1") (pinfunction "I0_1") (pintype "input"))
      (node (ref "E7") (pin "11") (pinfunction "O_11") (pintype "output"))
    )
    (net (code "81") (name "Net-(E19A-I1)") (class "Default")
      (node (ref "E19") (pin "2") (pinfunction "I1_2") (pintype "input"))
      (node (ref "E7") (pin "3") (pinfunction "O_3") (pintype "output"))
    )
    (net (code "82") (name "Net-(E19B-I0)") (class "Default")
      (node (ref "E19") (pin "6") (pinfunction "I0_6") (pintype "input"))
      (node (ref "E7") (pin "8") (pinfunction "O_8") (pintype "output"))
    )
    (net (code "83") (name "Net-(E19B-I1)") (class "Default")
      (node (ref "E19") (pin "7") (pinfunction "I1_7") (pintype "input"))
      (node (ref "E7") (pin "6") (pinfunction "O_6") (pintype "output"))
    )
    (net (code "84") (name "Net-(E20A-I0)") (class "Default")
      (node (ref "E20") (pin "1") (pinfunction "I0_1") (pintype "input"))
      (node (ref "E8") (pin "11") (pinfunction "O_11") (pintype "output"))
    )
    (net (code "85") (name "Net-(E20A-I1)") (class "Default")
      (node (ref "E20") (pin "2") (pinfunction "I1_2") (pintype "input"))
      (node (ref "E8") (pin "3") (pinfunction "O_3") (pintype "output"))
    )
    (net (code "86") (name "Net-(E20B-I0)") (class "Default")
      (node (ref "E20") (pin "6") (pinfunction "I0_6") (pintype "input"))
      (node (ref "E8") (pin "8") (pinfunction "O_8") (pintype "output"))
    )
    (net (code "87") (name "Net-(E20B-I1)") (class "Default")
      (node (ref "E20") (pin "7") (pinfunction "I1_7") (pintype "input"))
      (node (ref "E8") (pin "6") (pinfunction "O_6") (pintype "output"))
    )
    (net (code "88") (name "Net-(Q1-PadB1)") (class "Default")
      (node (ref "Q1") (pin "B1") (pinfunction "B1_B1") (pintype "passive"))
      (node (ref "R15") (pin "1") (pinfunction "1_1") (pintype "passive"))
    )
    (net (code "89") (name "Net-(Q1-PadB2)") (class "Default")
      (node (ref "Q1") (pin "B2") (pinfunction "B2_B2") (pintype "passive"))
      (node (ref "R16") (pin "2") (pinfunction "2_2") (pintype "passive"))
    )
    (net (code "90") (name "OSC_L") (class "Default")
      (node (ref "AB03") (pin "BF2") (pinfunction "1_BF2") (pintype "bidirectional"))
      (node (ref "E14") (pin "13") (pinfunction "I2_13") (pintype "input"))
      (node (ref "R5") (pin "1") (pinfunction "1_1") (pintype "passive"))
    )
    (net (code "91") (name "RANDOM_L") (class "Default")
      (node (ref "AB03") (pin "AR2") (pinfunction "1_AR2") (pintype "bidirectional"))
      (node (ref "E1") (pin "3") (pinfunction "I_3") (pintype "input"))
      (node (ref "R4") (pin "1") (pinfunction "1_1") (pintype "passive"))
    )
    (net (code "92") (name "REV_L") (class "Default")
      (node (ref "AB03") (pin "AE1") (pinfunction "1_AE1") (pintype "bidirectional"))
      (node (ref "E14") (pin "5") (pinfunction "I2_5") (pintype "input"))
      (node (ref "E17") (pin "13") (pinfunction "I1_13") (pintype "input"))
      (node (ref "R6") (pin "1") (pinfunction "1_1") (pintype "passive"))
    )
    (net (code "93") (name "RTZ_L") (class "Default")
      (node (ref "AB03") (pin "AB1") (pinfunction "1_AB1") (pintype "bidirectional"))
      (node (ref "E14") (pin "1") (pinfunction "I0_1") (pintype "input"))
      (node (ref "E17") (pin "2") (pinfunction "I1_2") (pintype "input"))
      (node (ref "E22") (pin "7") (pinfunction "I1_7") (pintype "input"))
      (node (ref "R1") (pin "1") (pinfunction "1_1") (pintype "passive"))
    )
    (net (code "94") (name "RUN_L") (class "Default")
      (node (ref "AB03") (pin "AA1") (pinfunction "1_AA1") (pintype "bidirectional"))
      (node (ref "E5") (pin "2") (pinfunction "I1_2") (pintype "input"))
      (node (ref "R11") (pin "1") (pinfunction "1_1") (pintype "passive"))
    )
    (net (code "95") (name "SEEK_INCOMPLETE_L") (class "Default")
      (node (ref "AB03") (pin "BE2") (pinfunction "1_BE2") (pintype "bidirectional"))
      (node (ref "E21") (pin "3") (pinfunction "O_3") (pintype "open_collector"))
    )
    (net (code "96") (name "STEP_L") (class "Default")
      (node (ref "AB03") (pin "AH2") (pinfunction "1_AH2") (pintype "bidirectional"))
      (node (ref "E18") (pin "1") (pinfunction "CLR_1") (pintype "input"))
      (node (ref "R8") (pin "1") (pinfunction "1_1") (pintype "passive"))
    )
    (net (code "97") (name "VCC") (class "Default")
      (node (ref "AB03") (pin "AA2") (pinfunction "1_AA2") (pintype "bidirectional"))
      (node (ref "AB03") (pin "BA2") (pinfunction "1_BA2") (pintype "bidirectional"))
      (node (ref "C1") (pin "1") (pinfunction "1_1") (pintype "passive"))
      (node (ref "C10") (pin "1") (pinfunction "1_1") (pintype "passive"))
      (node (ref "C11") (pin "1") (pinfunction "1_1") (pintype "passive"))
      (node (ref "C12") (pin "1") (pinfunction "1_1") (pintype "passive"))
      (node (ref "C13") (pin "1") (pinfunction "1_1") (pintype "passive"))
      (node (ref "C14") (pin "1") (pinfunction "1_1") (pintype "passive"))
      (node (ref "C15") (pin "1") (pinfunction "1_1") (pintype "passive"))
      (node (ref "C16") (pin "1") (pinfunction "1_1") (pintype "passive"))
      (node (ref "C17") (pin "1") (pinfunction "1_1") (pintype "passive"))
      (node (ref "C18") (pin "1") (pinfunction "1_1") (pintype "passive"))
      (node (ref "C19") (pin "1") (pinfunction "1_1") (pintype "passive"))
      (node (ref "C2") (pin "1") (pinfunction "1_1") (pintype "passive"))
      (node (ref "C20") (pin "1") (pinfunction "1_1") (pintype "passive"))
      (node (ref "C21") (pin "1") (pinfunction "1_1") (pintype "passive"))
      (node (ref "C22") (pin "+") (pinfunction "+_+") (pintype "passive"))
      (node (ref "C25") (pin "+") (pinfunction "+_+") (pintype "passive"))
      (node (ref "C3") (pin "1") (pinfunction "1_1") (pintype "passive"))
      (node (ref "C4") (pin "1") (pinfunction "1_1") (pintype "passive"))
      (node (ref "C5") (pin "1") (pinfunction "1_1") (pintype "passive"))
      (node (ref "C6") (pin "1") (pinfunction "1_1") (pintype "passive"))
      (node (ref "C7") (pin "1") (pinfunction "1_1") (pintype "passive"))
      (node (ref "C8") (pin "1") (pinfunction "1_1") (pintype "passive"))
      (node (ref "C9") (pin "1") (pinfunction "1_1") (pintype "passive"))
      (node (ref "D2") (pin "A") (pinfunction "A_A") (pintype "passive"))
      (node (ref "R1") (pin "2") (pinfunction "2_2") (pintype "passive"))
      (node (ref "R11") (pin "2") (pinfunction "2_2") (pintype "passive"))
      (node (ref "R12") (pin "2") (pinfunction "2_2") (pintype "passive"))
      (node (ref "R18") (pin "1") (pinfunction "1_1") (pintype "passive"))
      (node (ref "R19") (pin "1") (pinfunction "1_1") (pintype "passive"))
      (node (ref "R2") (pin "2") (pinfunction "2_2") (pintype "passive"))
      (node (ref "R20") (pin "1") (pinfunction "1_1") (pintype "passive"))
      (node (ref "R21") (pin "1") (pinfunction "1_1") (pintype "passive"))
      (node (ref "R22") (pin "1") (pinfunction "1_1") (pintype "passive"))
      (node (ref "R23") (pin "1") (pinfunction "1_1") (pintype "passive"))
      (node (ref "R24") (pin "1") (pinfunction "1_1") (pintype "passive"))
      (node (ref "R25") (pin "1") (pinfunction "1_1") (pintype "passive"))
      (node (ref "R26") (pin "2") (pinfunction "2_2") (pintype "passive"))
      (node (ref "R27") (pin "2") (pinfunction "2_2") (pintype "passive"))
      (node (ref "R4") (pin "2") (pinfunction "2_2") (pintype "passive"))
      (node (ref "R5") (pin "2") (pinfunction "2_2") (pintype "passive"))
      (node (ref "R6") (pin "2") (pinfunction "2_2") (pintype "passive"))
      (node (ref "R7") (pin "2") (pinfunction "2_2") (pintype "passive"))
      (node (ref "R8") (pin "2") (pinfunction "2_2") (pintype "passive"))
    )
    (net (code "98") (name "unconnected-(E2-ON1-Pad1)") (class "Default")
      (node (ref "E2") (pin "1") (pinfunction "ON1_1") (pintype "passive"))
    )
    (net (code "99") (name "unconnected-(E2-ON2-Pad5)") (class "Default")
      (node (ref "E2") (pin "5") (pinfunction "ON2_5") (pintype "passive"))
    )
    (net (code "100") (name "unconnected-(E2-OPT-Pad8)") (class "Default")
      (node (ref "E2") (pin "8") (pinfunction "OPT_8") (pintype "passive"))
    )
    (net (code "101") (name "unconnected-(E3A-Q-Pad13)") (class "Default")
      (node (ref "E3") (pin "13") (pinfunction "Q_13") (pintype "output"))
    )
    (net (code "102") (name "unconnected-(E3B-Q-Pad5)") (class "Default")
      (node (ref "E3") (pin "5") (pinfunction "Q_5") (pintype "output"))
    )
    (net (code "103") (name "unconnected-(E4B-O-Pad6)") (class "Default")
      (node (ref "E4") (pin "6") (pinfunction "O_6") (pintype "output"))
    )
    (net (code "104") (name "unconnected-(E4C-O-Pad8)") (class "Default")
      (node (ref "E4") (pin "8") (pinfunction "O_8") (pintype "output"))
    )
    (net (code "105") (name "unconnected-(E4D-O-Pad11)") (class "Default")
      (node (ref "E4") (pin "11") (pinfunction "O_11") (pintype "output"))
    )
    (net (code "106") (name "unconnected-(E6B-O-Pad8)") (class "Default")
      (node (ref "E6") (pin "8") (pinfunction "O_8") (pintype "output"))
    )
    (net (code "107") (name "unconnected-(E9A-BO-Pad13)") (class "Default")
      (node (ref "E9") (pin "13") (pinfunction "BO_13") (pintype "output"))
    )
    (net (code "108") (name "unconnected-(E9A-CO-Pad12)") (class "Default")
      (node (ref "E9") (pin "12") (pinfunction "CO_12") (pintype "output"))
    )
    (net (code "109") (name "unconnected-(E18B-Q-Pad9)") (class "Default")
      (node (ref "E18") (pin "9") (pinfunction "Q_9") (pintype "output"))
    )
    (net (code "110") (name "unconnected-(E18B-~{Q}-Pad8)") (class "Default")
      (node (ref "E18") (pin "8") (pinfunction "~{Q}_8") (pintype "output"))
    )
  )
)
